# max32620fthr.net
KiCad netlist of a schematic drawn in EAGLE
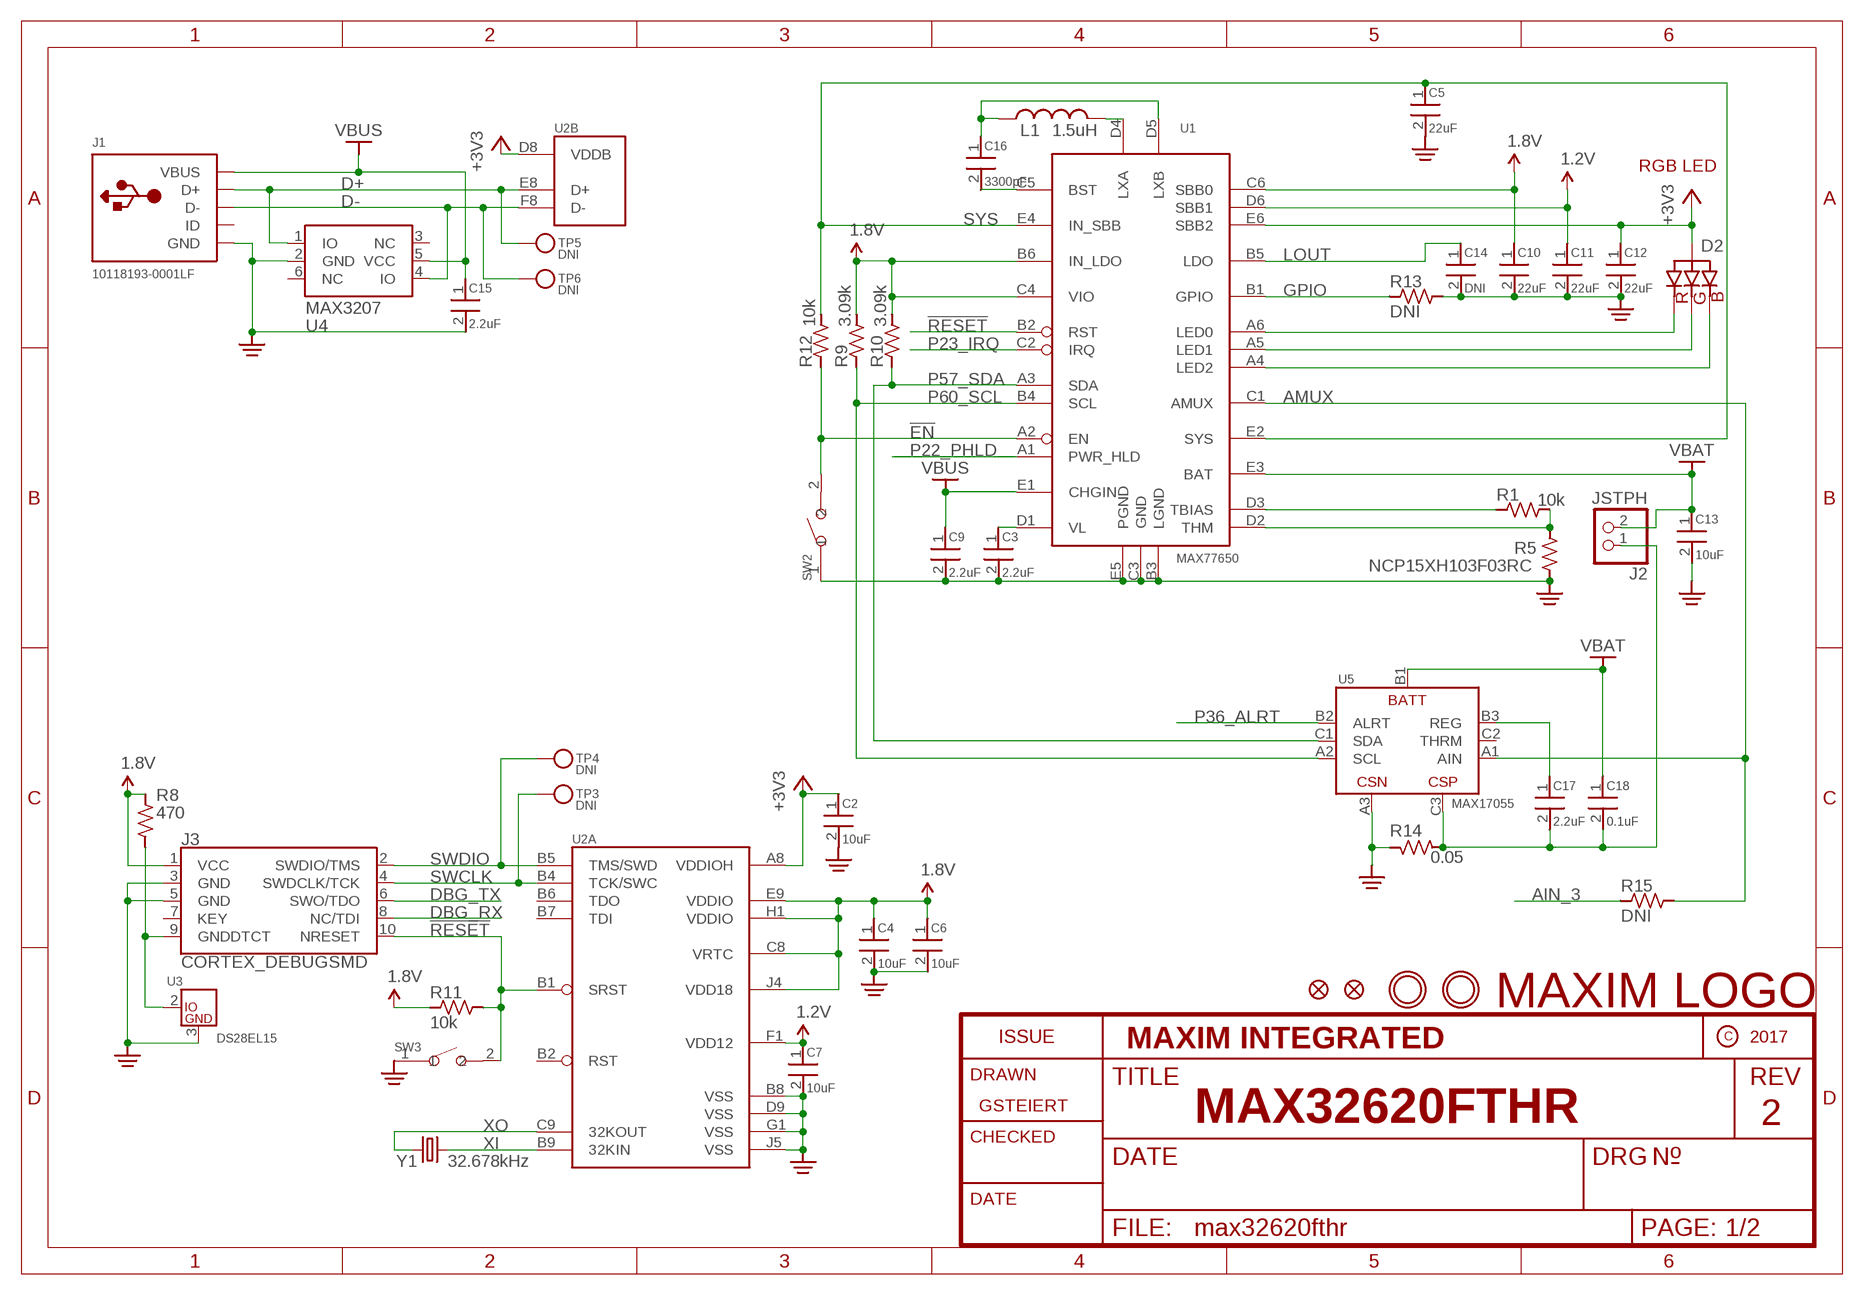
[diagram p0: schematic, sheet 1]
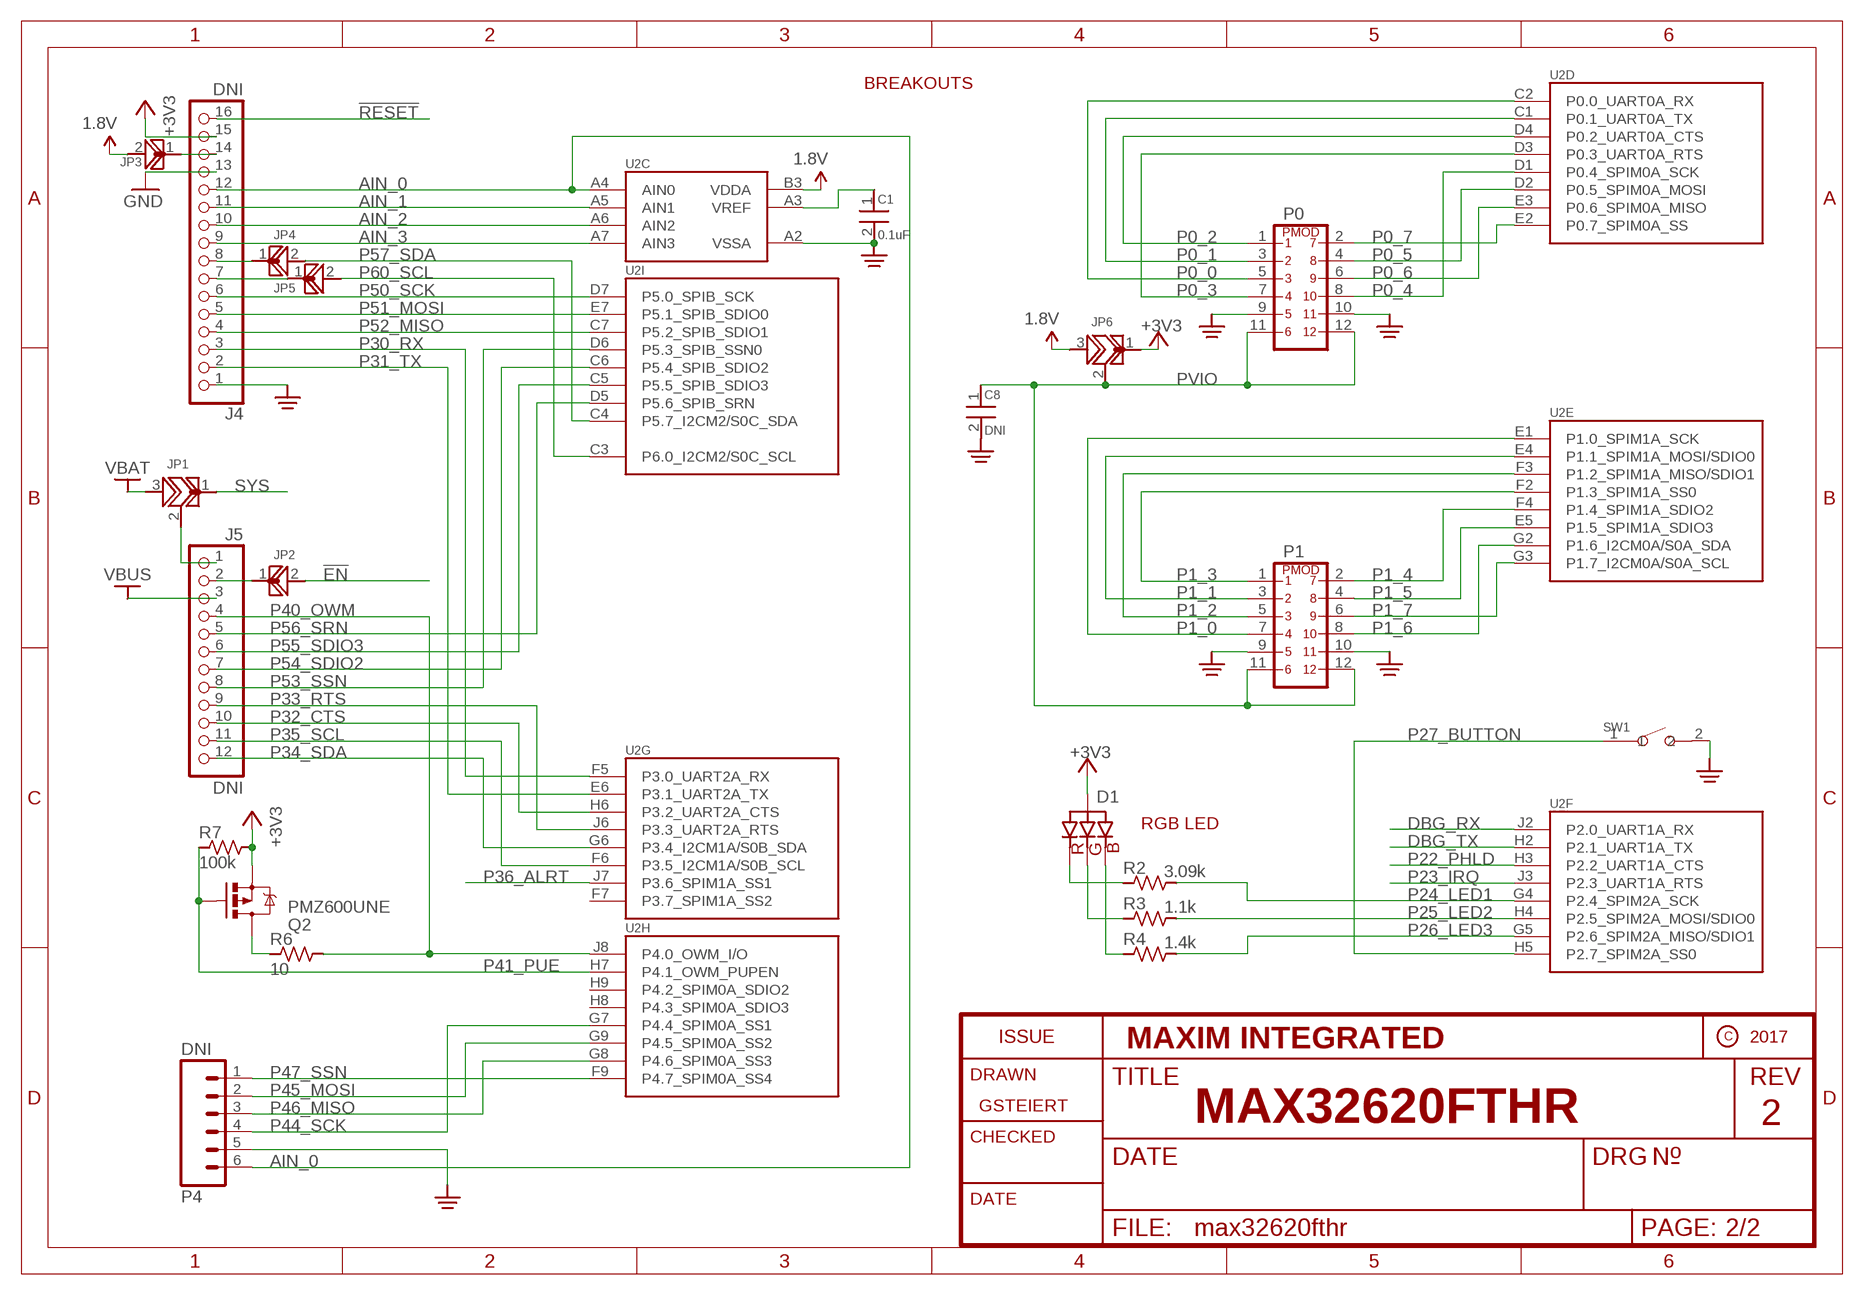
[diagram p1: schematic, sheet 2]

(export (version "E")
  (design (tool "Eeschema 10.0.6"))
  (components
    (comp (ref "C1")
      (value "0.1uF")
      (footprint "eagle-import:0402")
      (libsource (lib "eagle-import") (part "C0402"))
    )
    (comp (ref "C8")
      (value "DNI")
      (footprint "eagle-import:0402")
      (libsource (lib "eagle-import") (part "C0402"))
    )
    (comp (ref "D1")
      (value "RGBLED_CALUMIX-SML-LX0404")
      (footprint "eagle-import:LUMIX-SML-LX0404")
      (libsource (lib "eagle-import") (part "RGBLED_CALUMIX-SML-LX0404"))
    )
    (comp (ref "J4")
      (value "DNI")
      (footprint "eagle-import:1X16_ROUND")
      (libsource (lib "eagle-import") (part "HEADER-1X16ROUND"))
    )
    (comp (ref "J5")
      (value "DNI")
      (footprint "eagle-import:1X12_ROUND")
      (libsource (lib "eagle-import") (part "HEADER-1X12"))
    )
    (comp (ref "JP1")
      (value "DNI")
      (footprint "eagle-import:SS0402")
      (libsource (lib "eagle-import") (part "SOLDER_SELECTOR"))
    )
    (comp (ref "JP2")
      (value "DNI")
      (footprint "eagle-import:SB0402")
      (libsource (lib "eagle-import") (part "SOLDER_BRIDGE"))
    )
    (comp (ref "JP3")
      (value "DNI")
      (footprint "eagle-import:SB0402")
      (libsource (lib "eagle-import") (part "SOLDER_BRIDGE"))
    )
    (comp (ref "JP4")
      (value "DNI")
      (footprint "eagle-import:SB0402")
      (libsource (lib "eagle-import") (part "SOLDER_BRIDGE"))
    )
    (comp (ref "JP5")
      (value "DNI")
      (footprint "eagle-import:SB0402")
      (libsource (lib "eagle-import") (part "SOLDER_BRIDGE"))
    )
    (comp (ref "JP6")
      (value "DNI")
      (footprint "eagle-import:SS0402")
      (libsource (lib "eagle-import") (part "SOLDER_SELECTOR"))
    )
    (comp (ref "P0")
      (value "PMOD_DUALPASSTHROUGH")
      (footprint "eagle-import:2X6_HLE_BE")
      (libsource (lib "eagle-import") (part "PMOD_DUALPASSTHROUGH"))
    )
    (comp (ref "P1")
      (value "PMOD_DUALPASSTHROUGH")
      (footprint "eagle-import:2X6_HLE_BE")
      (libsource (lib "eagle-import") (part "PMOD_DUALPASSTHROUGH"))
    )
    (comp (ref "P4")
      (value "DNI")
      (footprint "eagle-import:1X06-SMD_EDGE")
      (libsource (lib "eagle-import") (part "M061X06-SMD_EDGE_FEMALE"))
    )
    (comp (ref "Q2")
      (value "PMZ600UNE")
      (footprint "eagle-import:SOT-883")
      (libsource (lib "eagle-import") (part "PMZ600UNE"))
    )
    (comp (ref "R2")
      (value "3.09k")
      (footprint "eagle-import:0402")
      (libsource (lib "eagle-import") (part "R"))
    )
    (comp (ref "R3")
      (value "1.1k")
      (footprint "eagle-import:0402")
      (libsource (lib "eagle-import") (part "R"))
    )
    (comp (ref "R4")
      (value "1.4k")
      (footprint "eagle-import:0402")
      (libsource (lib "eagle-import") (part "R"))
    )
    (comp (ref "R6") (value "10") (footprint "eagle-import:0402") (libsource (lib "eagle-import") (part "R")))
    (comp (ref "R7")
      (value "100k")
      (footprint "eagle-import:0402")
      (libsource (lib "eagle-import") (part "R"))
    )
    (comp (ref "SW1")
      (value "SMD-BUTTON(2P-3.0X2.5X1.2+0.4MM)-B3U-1000P-2P-SMD")
      (footprint "eagle-import:SW2-2.6-3.0X2.5X1.2+0.4MM")
      (libsource (lib "eagle-import") (part "SMD-BUTTON(2P-3.0X2.5X1.2+0.4MM)-B3U-1000P-2P-SMD"))
    )
    (comp (ref "U2")
      (value "MAX32620")
      (footprint "eagle-import:W813D3-1")
      (libsource (lib "eagle-import") (part "MAX32620"))
    )
    (comp (ref "C2")
      (value "10uF")
      (footprint "eagle-import:0402")
      (libsource (lib "eagle-import") (part "C0402"))
    )
    (comp (ref "C3")
      (value "2.2uF")
      (footprint "eagle-import:0402")
      (libsource (lib "eagle-import") (part "C0402"))
    )
    (comp (ref "C4")
      (value "10uF")
      (footprint "eagle-import:0402")
      (libsource (lib "eagle-import") (part "C0402"))
    )
    (comp (ref "C5")
      (value "22uF")
      (footprint "eagle-import:0402")
      (libsource (lib "eagle-import") (part "C0402"))
    )
    (comp (ref "C6")
      (value "10uF")
      (footprint "eagle-import:0402")
      (libsource (lib "eagle-import") (part "C0402"))
    )
    (comp (ref "C7")
      (value "10uF")
      (footprint "eagle-import:0402")
      (libsource (lib "eagle-import") (part "C0402"))
    )
    (comp (ref "C9")
      (value "2.2uF")
      (footprint "eagle-import:0402")
      (libsource (lib "eagle-import") (part "C0402"))
    )
    (comp (ref "C10")
      (value "22uF")
      (footprint "eagle-import:0402")
      (libsource (lib "eagle-import") (part "C0402"))
    )
    (comp (ref "C11")
      (value "22uF")
      (footprint "eagle-import:0402")
      (libsource (lib "eagle-import") (part "C0402"))
    )
    (comp (ref "C12")
      (value "22uF")
      (footprint "eagle-import:0402")
      (libsource (lib "eagle-import") (part "C0402"))
    )
    (comp (ref "C13")
      (value "10uF")
      (footprint "eagle-import:0402")
      (libsource (lib "eagle-import") (part "C0402"))
    )
    (comp (ref "C14")
      (value "DNI")
      (footprint "eagle-import:0402")
      (libsource (lib "eagle-import") (part "C0402"))
    )
    (comp (ref "C15")
      (value "2.2uF")
      (footprint "eagle-import:0402")
      (libsource (lib "eagle-import") (part "C0402"))
    )
    (comp (ref "C16")
      (value "3300pF")
      (footprint "eagle-import:0402")
      (libsource (lib "eagle-import") (part "C0402"))
    )
    (comp (ref "C17")
      (value "2.2uF")
      (footprint "eagle-import:0402")
      (libsource (lib "eagle-import") (part "C0402"))
    )
    (comp (ref "C18")
      (value "0.1uF")
      (footprint "eagle-import:0402")
      (libsource (lib "eagle-import") (part "C0402"))
    )
    (comp (ref "D2")
      (value "RGBLED_CALUMIX-SML-LX0404")
      (footprint "eagle-import:LUMIX-SML-LX0404")
      (libsource (lib "eagle-import") (part "RGBLED_CALUMIX-SML-LX0404"))
    )
    (comp (ref "J1")
      (value "10118193-0001LF")
      (footprint "eagle-import:MICRO-USB5+6P-SMD-0.65-B")
      (libsource (lib "eagle-import") (part "MICRO-USB-SMD-B-(10118193-0001LF)"))
    )
    (comp (ref "J2")
      (value "JSTPH")
      (footprint "eagle-import:JSTPH2")
      (libsource (lib "eagle-import") (part "CON_JST_PH_2PIN"))
    )
    (comp (ref "J3")
      (value "CORTEX_DEBUGSMD")
      (footprint "eagle-import:SAMTECH_FTSH-105-01")
      (libsource (lib "eagle-import") (part "CORTEX_DEBUGSMD"))
    )
    (comp (ref "L1")
      (value "1.5uH")
      (footprint "eagle-import:IND2016")
      (libsource (lib "eagle-import") (part "INDUCTOR2016"))
    )
    (comp (ref "R1")
      (value "10k")
      (footprint "eagle-import:0402")
      (libsource (lib "eagle-import") (part "R"))
    )
    (comp (ref "R5")
      (value "NCP15XH103F03RC")
      (footprint "eagle-import:0402")
      (libsource (lib "eagle-import") (part "R"))
    )
    (comp (ref "R8")
      (value "470")
      (footprint "eagle-import:0402")
      (libsource (lib "eagle-import") (part "R"))
    )
    (comp (ref "R9")
      (value "3.09k")
      (footprint "eagle-import:0402")
      (libsource (lib "eagle-import") (part "R"))
    )
    (comp (ref "R10")
      (value "3.09k")
      (footprint "eagle-import:0402")
      (libsource (lib "eagle-import") (part "R"))
    )
    (comp (ref "R11")
      (value "10k")
      (footprint "eagle-import:0402")
      (libsource (lib "eagle-import") (part "R"))
    )
    (comp (ref "R12")
      (value "10k")
      (footprint "eagle-import:0402")
      (libsource (lib "eagle-import") (part "R"))
    )
    (comp (ref "R13")
      (value "DNI")
      (footprint "eagle-import:0402")
      (libsource (lib "eagle-import") (part "R"))
    )
    (comp (ref "R14")
      (value "0.05")
      (footprint "eagle-import:0402")
      (libsource (lib "eagle-import") (part "R"))
    )
    (comp (ref "R15")
      (value "DNI")
      (footprint "eagle-import:0402")
      (libsource (lib "eagle-import") (part "R"))
    )
    (comp (ref "SW2")
      (value "SMD-BUTTON(2P-3.0X2.5X1.2+0.4MM)-B3U-1000P-2P-SMD")
      (footprint "eagle-import:SW2-2.6-3.0X2.5X1.2+0.4MM")
      (libsource (lib "eagle-import") (part "SMD-BUTTON(2P-3.0X2.5X1.2+0.4MM)-B3U-1000P-2P-SMD"))
    )
    (comp (ref "SW3")
      (value "SMD-BUTTON(2P-3.0X2.5X1.2+0.4MM)-B3U-1000P-2P-SMD")
      (footprint "eagle-import:SW2-2.6-3.0X2.5X1.2+0.4MM")
      (libsource (lib "eagle-import") (part "SMD-BUTTON(2P-3.0X2.5X1.2+0.4MM)-B3U-1000P-2P-SMD"))
    )
    (comp (ref "TP3")
      (value "DNI")
      (footprint "eagle-import:TESTPOINT_ROUND_1MM")
      (libsource (lib "eagle-import") (part "TESTPOINTROUND1MM"))
    )
    (comp (ref "TP4")
      (value "DNI")
      (footprint "eagle-import:TESTPOINT_ROUND_1MM")
      (libsource (lib "eagle-import") (part "TESTPOINTROUND1MM"))
    )
    (comp (ref "TP5")
      (value "DNI")
      (footprint "eagle-import:TESTPOINT_ROUND_1MM")
      (libsource (lib "eagle-import") (part "TESTPOINTROUND1MM"))
    )
    (comp (ref "TP6")
      (value "DNI")
      (footprint "eagle-import:TESTPOINT_ROUND_1MM")
      (libsource (lib "eagle-import") (part "TESTPOINTROUND1MM"))
    )
    (comp (ref "U$3")
      (value "DNI")
      (footprint "eagle-import:MXM_LOGO_6MM")
      (libsource (lib "eagle-import") (part "MAXIM_LOGO"))
    )
    (comp (ref "U$31")
      (value "DNI")
      (footprint "eagle-import:MOUNTINGHOLE_2.5_PLATED")
      (libsource (lib "eagle-import") (part "MOUNTINGHOLE2.5"))
    )
    (comp (ref "U$32")
      (value "DNI")
      (footprint "eagle-import:MOUNTINGHOLE_2.5_PLATED")
      (libsource (lib "eagle-import") (part "MOUNTINGHOLE2.5"))
    )
    (comp (ref "U$34")
      (value "DNI")
      (footprint "eagle-import:FIDUCIAL_1MM")
      (libsource (lib "eagle-import") (part "FIDUCIAL{dblquote}{dblquote}"))
    )
    (comp (ref "U$35")
      (value "DNI")
      (footprint "eagle-import:FIDUCIAL_1MM")
      (libsource (lib "eagle-import") (part "FIDUCIAL{dblquote}{dblquote}"))
    )
    (comp (ref "U1")
      (value "MAX77650")
      (footprint "eagle-import:W302H2-1")
      (libsource (lib "eagle-import") (part "MAX77650"))
    )
    (comp (ref "U3")
      (value "DS28EL15")
      (footprint "eagle-import:T633-2")
      (libsource (lib "eagle-import") (part "DS28EL15"))
    )
    (comp (ref "U4")
      (value "MAX3207")
      (footprint "eagle-import:SOT23-6")
      (libsource (lib "eagle-import") (part "MAX3207"))
    )
    (comp (ref "U5")
      (value "MAX17055")
      (footprint "eagle-import:W91N1-1")
      (libsource (lib "eagle-import") (part "MAX17055"))
    )
    (comp (ref "Y1")
      (value "32.678kHz")
      (footprint "eagle-import:FC-12M")
      (libsource (lib "eagle-import") (part "FC-12M"))
    )
  )
  (nets
    (net (code "1") (name "+3V3") (class "Default")
      (node (ref "C12") (pin "1") (pinfunction "1_1") (pintype "bidirectional"))
      (node (ref "C2") (pin "1") (pinfunction "1_1") (pintype "bidirectional"))
      (node (ref "D1") (pin "1") (pinfunction "VCC_1") (pintype "bidirectional"))
      (node (ref "D2") (pin "1") (pinfunction "VCC_1") (pintype "bidirectional"))
      (node (ref "J4") (pin "15") (pinfunction "15_15") (pintype "passive"))
      (node (ref "JP6") (pin "1") (pinfunction "1_1") (pintype "bidirectional"))
      (node (ref "Q2") (pin "2") (pinfunction "S_2") (pintype "passive"))
      (node (ref "R7") (pin "2") (pinfunction "2_2") (pintype "passive"))
      (node (ref "U1") (pin "E6") (pinfunction "SBB2_E6") (pintype "power_in"))
      (node (ref "U2") (pin "A8") (pinfunction "VDDIOH_A8") (pintype "power_in"))
      (node (ref "U2") (pin "D8") (pinfunction "VDDB_D8") (pintype "power_in"))
    )
    (net (code "2") (name "1.2V") (class "Default")
      (node (ref "C11") (pin "1") (pinfunction "1_1") (pintype "bidirectional"))
      (node (ref "C7") (pin "1") (pinfunction "1_1") (pintype "bidirectional"))
      (node (ref "U1") (pin "D6") (pinfunction "SBB1_D6") (pintype "power_in"))
      (node (ref "U2") (pin "F1") (pinfunction "VDD12_F1") (pintype "power_in"))
    )
    (net (code "3") (name "1.8V") (class "Default")
      (node (ref "C10") (pin "1") (pinfunction "1_1") (pintype "bidirectional"))
      (node (ref "C4") (pin "1") (pinfunction "1_1") (pintype "bidirectional"))
      (node (ref "C6") (pin "1") (pinfunction "1_1") (pintype "bidirectional"))
      (node (ref "J3") (pin "1") (pinfunction "VCC_1") (pintype "bidirectional"))
      (node (ref "JP3") (pin "2") (pinfunction "2_2") (pintype "bidirectional"))
      (node (ref "JP6") (pin "3") (pinfunction "3_3") (pintype "bidirectional"))
      (node (ref "R10") (pin "2") (pinfunction "2_2") (pintype "passive"))
      (node (ref "R11") (pin "1") (pinfunction "1_1") (pintype "passive"))
      (node (ref "R8") (pin "2") (pinfunction "2_2") (pintype "passive"))
      (node (ref "R9") (pin "2") (pinfunction "2_2") (pintype "passive"))
      (node (ref "U1") (pin "B6") (pinfunction "IN_LDO_B6") (pintype "power_in"))
      (node (ref "U1") (pin "C4") (pinfunction "VIO_C4") (pintype "power_in"))
      (node (ref "U1") (pin "C6") (pinfunction "SBB0_C6") (pintype "power_in"))
      (node (ref "U2") (pin "B3") (pinfunction "VDDA_B3") (pintype "power_in"))
      (node (ref "U2") (pin "C8") (pinfunction "VRTC_C8") (pintype "power_in"))
      (node (ref "U2") (pin "E9") (pinfunction "VDDIO_E9") (pintype "power_in"))
      (node (ref "U2") (pin "H1") (pinfunction "VDDIO_H1") (pintype "power_in"))
      (node (ref "U2") (pin "J4") (pinfunction "VDD18_J4") (pintype "power_in"))
    )
    (net (code "4") (name "AIN_0") (class "Default")
      (node (ref "J4") (pin "12") (pinfunction "12_12") (pintype "passive"))
      (node (ref "P4") (pin "6") (pinfunction "6_6") (pintype "passive"))
      (node (ref "U2") (pin "A4") (pinfunction "AIN0_A4") (pintype "input"))
    )
    (net (code "5") (name "AIN_1") (class "Default")
      (node (ref "J4") (pin "11") (pinfunction "11_11") (pintype "passive"))
      (node (ref "U2") (pin "A5") (pinfunction "AIN1_A5") (pintype "input"))
    )
    (net (code "6") (name "AIN_2") (class "Default")
      (node (ref "J4") (pin "10") (pinfunction "10_10") (pintype "passive"))
      (node (ref "U2") (pin "A6") (pinfunction "AIN2_A6") (pintype "input"))
    )
    (net (code "7") (name "AIN_3") (class "Default")
      (node (ref "J4") (pin "9") (pinfunction "9_9") (pintype "passive"))
      (node (ref "R15") (pin "1") (pinfunction "1_1") (pintype "passive"))
      (node (ref "U2") (pin "A7") (pinfunction "AIN3_A7") (pintype "input"))
    )
    (net (code "8") (name "AMUX") (class "Default")
      (node (ref "R15") (pin "2") (pinfunction "2_2") (pintype "passive"))
      (node (ref "U1") (pin "C1") (pinfunction "AMUX_C1") (pintype "output"))
      (node (ref "U5") (pin "A1") (pinfunction "AIN_A1") (pintype "input"))
    )
    (net (code "9") (name "D+") (class "Default")
      (node (ref "J1") (pin "3") (pinfunction "D+_3") (pintype "bidirectional"))
      (node (ref "TP5") (pin "P$1") (pinfunction "P$1_P$1") (pintype "bidirectional"))
      (node (ref "U2") (pin "E8") (pinfunction "D+_E8") (pintype "bidirectional"))
      (node (ref "U4") (pin "1") (pinfunction "IO_1") (pintype "bidirectional"))
    )
    (net (code "10") (name "D-") (class "Default")
      (node (ref "J1") (pin "2") (pinfunction "D-_2") (pintype "bidirectional"))
      (node (ref "TP6") (pin "P$1") (pinfunction "P$1_P$1") (pintype "bidirectional"))
      (node (ref "U2") (pin "F8") (pinfunction "D-_F8") (pintype "bidirectional"))
      (node (ref "U4") (pin "4") (pinfunction "IO_4") (pintype "bidirectional"))
    )
    (net (code "11") (name "DBG_RX") (class "Default")
      (node (ref "J3") (pin "8") (pinfunction "NC/TDI_8") (pintype "bidirectional"))
      (node (ref "U2") (pin "J2") (pinfunction "P2.0_UART1A_RX_J2") (pintype "bidirectional"))
    )
    (net (code "12") (name "DBG_TX") (class "Default")
      (node (ref "J3") (pin "6") (pinfunction "SWO/TDO_6") (pintype "bidirectional"))
      (node (ref "U2") (pin "H2") (pinfunction "P2.1_UART1A_TX_H2") (pintype "bidirectional"))
    )
    (net (code "13") (name "GND") (class "Default")
      (node (ref "C1") (pin "2") (pinfunction "2_2") (pintype "bidirectional"))
      (node (ref "C10") (pin "2") (pinfunction "2_2") (pintype "bidirectional"))
      (node (ref "C11") (pin "2") (pinfunction "2_2") (pintype "bidirectional"))
      (node (ref "C12") (pin "2") (pinfunction "2_2") (pintype "bidirectional"))
      (node (ref "C13") (pin "2") (pinfunction "2_2") (pintype "bidirectional"))
      (node (ref "C14") (pin "2") (pinfunction "2_2") (pintype "bidirectional"))
      (node (ref "C15") (pin "2") (pinfunction "2_2") (pintype "bidirectional"))
      (node (ref "C2") (pin "2") (pinfunction "2_2") (pintype "bidirectional"))
      (node (ref "C3") (pin "2") (pinfunction "2_2") (pintype "bidirectional"))
      (node (ref "C4") (pin "2") (pinfunction "2_2") (pintype "bidirectional"))
      (node (ref "C5") (pin "2") (pinfunction "2_2") (pintype "bidirectional"))
      (node (ref "C6") (pin "2") (pinfunction "2_2") (pintype "bidirectional"))
      (node (ref "C7") (pin "2") (pinfunction "2_2") (pintype "bidirectional"))
      (node (ref "C8") (pin "2") (pinfunction "2_2") (pintype "bidirectional"))
      (node (ref "C9") (pin "2") (pinfunction "2_2") (pintype "bidirectional"))
      (node (ref "J1") (pin "5") (pinfunction "GND_5") (pintype "power_in"))
      (node (ref "J1") (pin "S1") (pinfunction "GND_S1") (pintype "power_in"))
      (node (ref "J1") (pin "S2") (pinfunction "GND_S2") (pintype "power_in"))
      (node (ref "J1") (pin "S3") (pinfunction "GND_S3") (pintype "power_in"))
      (node (ref "J1") (pin "S4") (pinfunction "GND_S4") (pintype "power_in"))
      (node (ref "J1") (pin "S5") (pinfunction "GND_S5") (pintype "power_in"))
      (node (ref "J1") (pin "S6") (pinfunction "GND_S6") (pintype "power_in"))
      (node (ref "J3") (pin "3") (pinfunction "GND_3") (pintype "bidirectional"))
      (node (ref "J3") (pin "5") (pinfunction "GND_5") (pintype "bidirectional"))
      (node (ref "J4") (pin "1") (pinfunction "1_1") (pintype "passive"))
      (node (ref "J4") (pin "13") (pinfunction "13_13") (pintype "passive"))
      (node (ref "P0") (pin "10") (pinfunction "10_10") (pintype "passive"))
      (node (ref "P0") (pin "9") (pinfunction "9_9") (pintype "passive"))
      (node (ref "P1") (pin "10") (pinfunction "10_10") (pintype "passive"))
      (node (ref "P1") (pin "9") (pinfunction "9_9") (pintype "passive"))
      (node (ref "P4") (pin "5") (pinfunction "5_5") (pintype "passive"))
      (node (ref "R13") (pin "2") (pinfunction "2_2") (pintype "passive"))
      (node (ref "R14") (pin "2") (pinfunction "2_2") (pintype "passive"))
      (node (ref "R5") (pin "2") (pinfunction "2_2") (pintype "passive"))
      (node (ref "SW1") (pin "2") (pinfunction "2_2") (pintype "bidirectional"))
      (node (ref "SW2") (pin "1") (pinfunction "1_1") (pintype "bidirectional"))
      (node (ref "SW3") (pin "1") (pinfunction "1_1") (pintype "bidirectional"))
      (node (ref "U1") (pin "B3") (pinfunction "LGND_B3") (pintype "power_in"))
      (node (ref "U1") (pin "C3") (pinfunction "GND_C3") (pintype "power_in"))
      (node (ref "U1") (pin "E5") (pinfunction "PGND_E5") (pintype "power_in"))
      (node (ref "U2") (pin "A2") (pinfunction "VSSA_A2") (pintype "power_in"))
      (node (ref "U2") (pin "B8") (pinfunction "VSS_B8") (pintype "power_in"))
      (node (ref "U2") (pin "D9") (pinfunction "VSS_D9") (pintype "power_in"))
      (node (ref "U2") (pin "G1") (pinfunction "VSS_G1") (pintype "power_in"))
      (node (ref "U2") (pin "J5") (pinfunction "VSS_J5") (pintype "power_in"))
      (node (ref "U3") (pin "3") (pinfunction "GND_3") (pintype "power_in"))
      (node (ref "U4") (pin "2") (pinfunction "GND_2") (pintype "power_in"))
      (node (ref "U5") (pin "A3") (pinfunction "CSN_A3") (pintype "output"))
    )
    (net (code "14") (name "GPIO") (class "Default")
      (node (ref "R13") (pin "1") (pinfunction "1_1") (pintype "passive"))
      (node (ref "U1") (pin "B1") (pinfunction "GPIO_B1") (pintype "bidirectional"))
    )
    (net (code "15") (name "LOUT") (class "Default")
      (node (ref "C14") (pin "1") (pinfunction "1_1") (pintype "bidirectional"))
      (node (ref "U1") (pin "B5") (pinfunction "LDO_B5") (pintype "power_in"))
    )
    (net (code "16") (name "Net-(D1-BLUE)") (class "Default")
      (node (ref "D1") (pin "3") (pinfunction "BLUE_3") (pintype "bidirectional"))
      (node (ref "R4") (pin "1") (pinfunction "1_1") (pintype "passive"))
    )
    (net (code "17") (name "Net-(D1-GREEN)") (class "Default")
      (node (ref "D1") (pin "4") (pinfunction "GREEN_4") (pintype "bidirectional"))
      (node (ref "R3") (pin "1") (pinfunction "1_1") (pintype "passive"))
    )
    (net (code "18") (name "Net-(D1-RED)") (class "Default")
      (node (ref "D1") (pin "2") (pinfunction "RED_2") (pintype "bidirectional"))
      (node (ref "R2") (pin "1") (pinfunction "1_1") (pintype "passive"))
    )
    (net (code "19") (name "Net-(D2-BLUE)") (class "Default")
      (node (ref "D2") (pin "3") (pinfunction "BLUE_3") (pintype "bidirectional"))
      (node (ref "U1") (pin "A4") (pinfunction "LED2_A4") (pintype "output"))
    )
    (net (code "20") (name "Net-(D2-GREEN)") (class "Default")
      (node (ref "D2") (pin "4") (pinfunction "GREEN_4") (pintype "bidirectional"))
      (node (ref "U1") (pin "A5") (pinfunction "LED1_A5") (pintype "output"))
    )
    (net (code "21") (name "Net-(D2-RED)") (class "Default")
      (node (ref "D2") (pin "2") (pinfunction "RED_2") (pintype "bidirectional"))
      (node (ref "U1") (pin "A6") (pinfunction "LED0_A6") (pintype "output"))
    )
    (net (code "22") (name "Net-(J3-GNDDTCT)") (class "Default")
      (node (ref "J3") (pin "9") (pinfunction "GNDDTCT_9") (pintype "bidirectional"))
      (node (ref "R8") (pin "1") (pinfunction "1_1") (pintype "passive"))
      (node (ref "U3") (pin "2") (pinfunction "IO_2") (pintype "bidirectional"))
    )
    (net (code "23") (name "Net-(J4-Pad7)") (class "Default")
      (node (ref "J4") (pin "7") (pinfunction "7_7") (pintype "passive"))
      (node (ref "JP5") (pin "1") (pinfunction "1_1") (pintype "bidirectional"))
    )
    (net (code "24") (name "Net-(J4-Pad8)") (class "Default")
      (node (ref "J4") (pin "8") (pinfunction "8_8") (pintype "passive"))
      (node (ref "JP4") (pin "1") (pinfunction "1_1") (pintype "bidirectional"))
    )
    (net (code "25") (name "Net-(J4-Pad14)") (class "Default")
      (node (ref "J4") (pin "14") (pinfunction "14_14") (pintype "passive"))
      (node (ref "JP3") (pin "1") (pinfunction "1_1") (pintype "bidirectional"))
    )
    (net (code "26") (name "Net-(J5-Pad1)") (class "Default")
      (node (ref "J5") (pin "1") (pinfunction "1_1") (pintype "passive"))
      (node (ref "JP1") (pin "2") (pinfunction "2_2") (pintype "bidirectional"))
    )
    (net (code "27") (name "Net-(J5-Pad2)") (class "Default")
      (node (ref "J5") (pin "2") (pinfunction "2_2") (pintype "passive"))
      (node (ref "JP2") (pin "1") (pinfunction "1_1") (pintype "bidirectional"))
    )
    (net (code "28") (name "Net-(Q2-D)") (class "Default")
      (node (ref "Q2") (pin "3") (pinfunction "D_3") (pintype "passive"))
      (node (ref "R6") (pin "1") (pinfunction "1_1") (pintype "passive"))
    )
    (net (code "29") (name "Net-(U1-BST)") (class "Default")
      (node (ref "C16") (pin "2") (pinfunction "2_2") (pintype "bidirectional"))
      (node (ref "U1") (pin "C5") (pinfunction "BST_C5") (pintype "power_in"))
    )
    (net (code "30") (name "Net-(U1-LXA)") (class "Default")
      (node (ref "L1") (pin "2") (pinfunction "2_2") (pintype "passive"))
      (node (ref "U1") (pin "D4") (pinfunction "LXA_D4") (pintype "power_in"))
    )
    (net (code "31") (name "Net-(U1-LXB)") (class "Default")
      (node (ref "C16") (pin "1") (pinfunction "1_1") (pintype "bidirectional"))
      (node (ref "L1") (pin "1") (pinfunction "1_1") (pintype "passive"))
      (node (ref "U1") (pin "D5") (pinfunction "LXB_D5") (pintype "power_in"))
    )
    (net (code "32") (name "Net-(U1-TBIAS)") (class "Default")
      (node (ref "R1") (pin "1") (pinfunction "1_1") (pintype "passive"))
      (node (ref "U1") (pin "D3") (pinfunction "TBIAS_D3") (pintype "output"))
    )
    (net (code "33") (name "Net-(U1-THM)") (class "Default")
      (node (ref "R1") (pin "2") (pinfunction "2_2") (pintype "passive"))
      (node (ref "R5") (pin "1") (pinfunction "1_1") (pintype "passive"))
      (node (ref "U1") (pin "D2") (pinfunction "THM_D2") (pintype "input"))
    )
    (net (code "34") (name "Net-(U1-VL)") (class "Default")
      (node (ref "C3") (pin "1") (pinfunction "1_1") (pintype "bidirectional"))
      (node (ref "U1") (pin "D1") (pinfunction "VL_D1") (pintype "power_in"))
    )
    (net (code "35") (name "Net-(U2C-VREF)") (class "Default")
      (node (ref "C1") (pin "1") (pinfunction "1_1") (pintype "bidirectional"))
      (node (ref "U2") (pin "A3") (pinfunction "VREF_A3") (pintype "power_in"))
    )
    (net (code "36") (name "Net-(U5-CSP)") (class "Default")
      (node (ref "C17") (pin "2") (pinfunction "2_2") (pintype "bidirectional"))
      (node (ref "C18") (pin "2") (pinfunction "2_2") (pintype "bidirectional"))
      (node (ref "J2") (pin "1") (pinfunction "1_1") (pintype "passive"))
      (node (ref "R14") (pin "1") (pinfunction "1_1") (pintype "passive"))
      (node (ref "U5") (pin "C3") (pinfunction "CSP_C3") (pintype "power_in"))
    )
    (net (code "37") (name "Net-(U5-REG)") (class "Default")
      (node (ref "C17") (pin "1") (pinfunction "1_1") (pintype "bidirectional"))
      (node (ref "U5") (pin "B3") (pinfunction "REG_B3") (pintype "power_in"))
    )
    (net (code "38") (name "P0_0") (class "Default")
      (node (ref "P0") (pin "5") (pinfunction "5_5") (pintype "passive"))
      (node (ref "U2") (pin "C2") (pinfunction "P0.0_UART0A_RX_C2") (pintype "bidirectional"))
    )
    (net (code "39") (name "P0_1") (class "Default")
      (node (ref "P0") (pin "3") (pinfunction "3_3") (pintype "passive"))
      (node (ref "U2") (pin "C1") (pinfunction "P0.1_UART0A_TX_C1") (pintype "bidirectional"))
    )
    (net (code "40") (name "P0_2") (class "Default")
      (node (ref "P0") (pin "1") (pinfunction "1_1") (pintype "passive"))
      (node (ref "U2") (pin "D4") (pinfunction "P0.2_UART0A_CTS_D4") (pintype "bidirectional"))
    )
    (net (code "41") (name "P0_3") (class "Default")
      (node (ref "P0") (pin "7") (pinfunction "7_7") (pintype "passive"))
      (node (ref "U2") (pin "D3") (pinfunction "P0.3_UART0A_RTS_D3") (pintype "bidirectional"))
    )
    (net (code "42") (name "P0_4") (class "Default")
      (node (ref "P0") (pin "8") (pinfunction "8_8") (pintype "passive"))
      (node (ref "U2") (pin "D1") (pinfunction "P0.4_SPIM0A_SCK_D1") (pintype "bidirectional"))
    )
    (net (code "43") (name "P0_5") (class "Default")
      (node (ref "P0") (pin "4") (pinfunction "4_4") (pintype "passive"))
      (node (ref "U2") (pin "D2") (pinfunction "P0.5_SPIM0A_MOSI_D2") (pintype "bidirectional"))
    )
    (net (code "44") (name "P0_6") (class "Default")
      (node (ref "P0") (pin "6") (pinfunction "6_6") (pintype "passive"))
      (node (ref "U2") (pin "E3") (pinfunction "P0.6_SPIM0A_MISO_E3") (pintype "bidirectional"))
    )
    (net (code "45") (name "P0_7") (class "Default")
      (node (ref "P0") (pin "2") (pinfunction "2_2") (pintype "passive"))
      (node (ref "U2") (pin "E2") (pinfunction "P0.7_SPIM0A_SS_E2") (pintype "bidirectional"))
    )
    (net (code "46") (name "P1_0") (class "Default")
      (node (ref "P1") (pin "7") (pinfunction "7_7") (pintype "passive"))
      (node (ref "U2") (pin "E1") (pinfunction "P1.0_SPIM1A_SCK_E1") (pintype "bidirectional"))
    )
    (net (code "47") (name "P1_1") (class "Default")
      (node (ref "P1") (pin "3") (pinfunction "3_3") (pintype "passive"))
      (node (ref "U2") (pin "E4") (pinfunction "P1.1_SPIM1A_MOSI/SDIO0_E4") (pintype "bidirectional"))
    )
    (net (code "48") (name "P1_2") (class "Default")
      (node (ref "P1") (pin "5") (pinfunction "5_5") (pintype "passive"))
      (node (ref "U2") (pin "F3") (pinfunction "P1.2_SPIM1A_MISO/SDIO1_F3") (pintype "bidirectional"))
    )
    (net (code "49") (name "P1_3") (class "Default")
      (node (ref "P1") (pin "1") (pinfunction "1_1") (pintype "passive"))
      (node (ref "U2") (pin "F2") (pinfunction "P1.3_SPIM1A_SS0_F2") (pintype "bidirectional"))
    )
    (net (code "50") (name "P1_4") (class "Default")
      (node (ref "P1") (pin "2") (pinfunction "2_2") (pintype "passive"))
      (node (ref "U2") (pin "F4") (pinfunction "P1.4_SPIM1A_SDIO2_F4") (pintype "bidirectional"))
    )
    (net (code "51") (name "P1_5") (class "Default")
      (node (ref "P1") (pin "4") (pinfunction "4_4") (pintype "passive"))
      (node (ref "U2") (pin "E5") (pinfunction "P1.5_SPIM1A_SDIO3_E5") (pintype "bidirectional"))
    )
    (net (code "52") (name "P1_6") (class "Default")
      (node (ref "P1") (pin "8") (pinfunction "8_8") (pintype "passive"))
      (node (ref "U2") (pin "G2") (pinfunction "P1.6_I2CM0A/S0A_SDA_G2") (pintype "bidirectional"))
    )
    (net (code "53") (name "P1_7") (class "Default")
      (node (ref "P1") (pin "6") (pinfunction "6_6") (pintype "passive"))
      (node (ref "U2") (pin "G3") (pinfunction "P1.7_I2CM0A/S0A_SCL_G3") (pintype "bidirectional"))
    )
    (net (code "54") (name "P22_PHLD") (class "Default")
      (node (ref "U1") (pin "A1") (pinfunction "PWR_HLD_A1") (pintype "open_collector"))
      (node (ref "U2") (pin "H3") (pinfunction "P2.2_UART1A_CTS_H3") (pintype "bidirectional"))
    )
    (net (code "55") (name "P23_IRQ") (class "Default")
      (node (ref "U1") (pin "C2") (pinfunction "IRQ_C2") (pintype "output"))
      (node (ref "U2") (pin "J3") (pinfunction "P2.3_UART1A_RTS_J3") (pintype "bidirectional"))
    )
    (net (code "56") (name "P24_LED1") (class "Default")
      (node (ref "R2") (pin "2") (pinfunction "2_2") (pintype "passive"))
      (node (ref "U2") (pin "G4") (pinfunction "P2.4_SPIM2A_SCK_G4") (pintype "bidirectional"))
    )
    (net (code "57") (name "P25_LED2") (class "Default")
      (node (ref "R3") (pin "2") (pinfunction "2_2") (pintype "passive"))
      (node (ref "U2") (pin "H4") (pinfunction "P2.5_SPIM2A_MOSI/SDIO0_H4") (pintype "bidirectional"))
    )
    (net (code "58") (name "P26_LED3") (class "Default")
      (node (ref "R4") (pin "2") (pinfunction "2_2") (pintype "passive"))
      (node (ref "U2") (pin "G5") (pinfunction "P2.6_SPIM2A_MISO/SDIO1_G5") (pintype "bidirectional"))
    )
    (net (code "59") (name "P27_BUTTON") (class "Default")
      (node (ref "SW1") (pin "1") (pinfunction "1_1") (pintype "bidirectional"))
      (node (ref "U2") (pin "H5") (pinfunction "P2.7_SPIM2A_SS0_H5") (pintype "bidirectional"))
    )
    (net (code "60") (name "P30_RX") (class "Default")
      (node (ref "J4") (pin "3") (pinfunction "3_3") (pintype "passive"))
      (node (ref "U2") (pin "F5") (pinfunction "P3.0_UART2A_RX_F5") (pintype "bidirectional"))
    )
    (net (code "61") (name "P31_TX") (class "Default")
      (node (ref "J4") (pin "2") (pinfunction "2_2") (pintype "passive"))
      (node (ref "U2") (pin "E6") (pinfunction "P3.1_UART2A_TX_E6") (pintype "bidirectional"))
    )
    (net (code "62") (name "P32_CTS") (class "Default")
      (node (ref "J5") (pin "10") (pinfunction "10_10") (pintype "passive"))
      (node (ref "U2") (pin "H6") (pinfunction "P3.2_UART2A_CTS_H6") (pintype "bidirectional"))
    )
    (net (code "63") (name "P33_RTS") (class "Default")
      (node (ref "J5") (pin "9") (pinfunction "9_9") (pintype "passive"))
      (node (ref "U2") (pin "J6") (pinfunction "P3.3_UART2A_RTS_J6") (pintype "bidirectional"))
    )
    (net (code "64") (name "P34_SDA") (class "Default")
      (node (ref "J5") (pin "12") (pinfunction "12_12") (pintype "passive"))
      (node (ref "U2") (pin "G6") (pinfunction "P3.4_I2CM1A/S0B_SDA_G6") (pintype "bidirectional"))
    )
    (net (code "65") (name "P35_SCL") (class "Default")
      (node (ref "J5") (pin "11") (pinfunction "11_11") (pintype "passive"))
      (node (ref "U2") (pin "F6") (pinfunction "P3.5_I2CM1A/S0B_SCL_F6") (pintype "bidirectional"))
    )
    (net (code "66") (name "P36_ALRT") (class "Default")
      (node (ref "U2") (pin "J7") (pinfunction "P3.6_SPIM1A_SS1_J7") (pintype "bidirectional"))
      (node (ref "U5") (pin "B2") (pinfunction "ALRT_B2") (pintype "output"))
    )
    (net (code "67") (name "P40_OWM") (class "Default")
      (node (ref "J5") (pin "4") (pinfunction "4_4") (pintype "passive"))
      (node (ref "R6") (pin "2") (pinfunction "2_2") (pintype "passive"))
      (node (ref "U2") (pin "J8") (pinfunction "P4.0_OWM_I/O_J8") (pintype "bidirectional"))
    )
    (net (code "68") (name "P41_PUE") (class "Default")
      (node (ref "Q2") (pin "1") (pinfunction "G_1") (pintype "passive"))
      (node (ref "R7") (pin "1") (pinfunction "1_1") (pintype "passive"))
      (node (ref "U2") (pin "H7") (pinfunction "P4.1_OWM_PUPEN_H7") (pintype "bidirectional"))
    )
    (net (code "69") (name "P44_SCK") (class "Default")
      (node (ref "P4") (pin "4") (pinfunction "4_4") (pintype "passive"))
      (node (ref "U2") (pin "G7") (pinfunction "P4.4_SPIM0A_SS1_G7") (pintype "bidirectional"))
    )
    (net (code "70") (name "P45_MOSI") (class "Default")
      (node (ref "P4") (pin "2") (pinfunction "2_2") (pintype "passive"))
      (node (ref "U2") (pin "G9") (pinfunction "P4.5_SPIM0A_SS2_G9") (pintype "bidirectional"))
    )
    (net (code "71") (name "P46_MISO") (class "Default")
      (node (ref "P4") (pin "3") (pinfunction "3_3") (pintype "passive"))
      (node (ref "U2") (pin "G8") (pinfunction "P4.6_SPIM0A_SS3_G8") (pintype "bidirectional"))
    )
    (net (code "72") (name "P47_SSN") (class "Default")
      (node (ref "P4") (pin "1") (pinfunction "1_1") (pintype "passive"))
      (node (ref "U2") (pin "F9") (pinfunction "P4.7_SPIM0A_SS4_F9") (pintype "bidirectional"))
    )
    (net (code "73") (name "P50_SCK") (class "Default")
      (node (ref "J4") (pin "6") (pinfunction "6_6") (pintype "passive"))
      (node (ref "U2") (pin "D7") (pinfunction "P5.0_SPIB_SCK_D7") (pintype "bidirectional"))
    )
    (net (code "74") (name "P51_MOSI") (class "Default")
      (node (ref "J4") (pin "5") (pinfunction "5_5") (pintype "passive"))
      (node (ref "U2") (pin "E7") (pinfunction "P5.1_SPIB_SDIO0_E7") (pintype "bidirectional"))
    )
    (net (code "75") (name "P52_MISO") (class "Default")
      (node (ref "J4") (pin "4") (pinfunction "4_4") (pintype "passive"))
      (node (ref "U2") (pin "C7") (pinfunction "P5.2_SPIB_SDIO1_C7") (pintype "bidirectional"))
    )
    (net (code "76") (name "P53_SSN") (class "Default")
      (node (ref "J5") (pin "8") (pinfunction "8_8") (pintype "passive"))
      (node (ref "U2") (pin "D6") (pinfunction "P5.3_SPIB_SSN0_D6") (pintype "bidirectional"))
    )
    (net (code "77") (name "P54_SDIO2") (class "Default")
      (node (ref "J5") (pin "7") (pinfunction "7_7") (pintype "passive"))
      (node (ref "U2") (pin "C6") (pinfunction "P5.4_SPIB_SDIO2_C6") (pintype "bidirectional"))
    )
    (net (code "78") (name "P55_SDIO3") (class "Default")
      (node (ref "J5") (pin "6") (pinfunction "6_6") (pintype "passive"))
      (node (ref "U2") (pin "C5") (pinfunction "P5.5_SPIB_SDIO3_C5") (pintype "bidirectional"))
    )
    (net (code "79") (name "P56_SRN") (class "Default")
      (node (ref "J5") (pin "5") (pinfunction "5_5") (pintype "passive"))
      (node (ref "U2") (pin "D5") (pinfunction "P5.6_SPIB_SRN_D5") (pintype "bidirectional"))
    )
    (net (code "80") (name "P57_SDA") (class "Default")
      (node (ref "JP4") (pin "2") (pinfunction "2_2") (pintype "bidirectional"))
      (node (ref "R10") (pin "1") (pinfunction "1_1") (pintype "passive"))
      (node (ref "U1") (pin "A3") (pinfunction "SDA_A3") (pintype "bidirectional"))
      (node (ref "U2") (pin "C4") (pinfunction "P5.7_I2CM2/S0C_SDA_C4") (pintype "bidirectional"))
      (node (ref "U5") (pin "C1") (pinfunction "SDA_C1") (pintype "bidirectional"))
    )
    (net (code "81") (name "P60_SCL") (class "Default")
      (node (ref "JP5") (pin "2") (pinfunction "2_2") (pintype "bidirectional"))
      (node (ref "R9") (pin "1") (pinfunction "1_1") (pintype "passive"))
      (node (ref "U1") (pin "B4") (pinfunction "SCL_B4") (pintype "input"))
      (node (ref "U2") (pin "C3") (pinfunction "P6.0_I2CM2/S0C_SCL_C3") (pintype "bidirectional"))
      (node (ref "U5") (pin "A2") (pinfunction "SCL_A2") (pintype "bidirectional"))
    )
    (net (code "82") (name "PVIO") (class "Default")
      (node (ref "C8") (pin "1") (pinfunction "1_1") (pintype "bidirectional"))
      (node (ref "JP6") (pin "2") (pinfunction "2_2") (pintype "bidirectional"))
      (node (ref "P0") (pin "11") (pinfunction "11_11") (pintype "passive"))
      (node (ref "P0") (pin "12") (pinfunction "12_12") (pintype "passive"))
      (node (ref "P1") (pin "11") (pinfunction "11_11") (pintype "passive"))
      (node (ref "P1") (pin "12") (pinfunction "12_12") (pintype "passive"))
    )
    (net (code "83") (name "SWCLK") (class "Default")
      (node (ref "J3") (pin "4") (pinfunction "SWDCLK/TCK_4") (pintype "bidirectional"))
      (node (ref "TP3") (pin "P$1") (pinfunction "P$1_P$1") (pintype "bidirectional"))
      (node (ref "U2") (pin "B4") (pinfunction "TCK/SWC_B4") (pintype "input"))
    )
    (net (code "84") (name "SWDIO") (class "Default")
      (node (ref "J3") (pin "2") (pinfunction "SWDIO/TMS_2") (pintype "bidirectional"))
      (node (ref "TP4") (pin "P$1") (pinfunction "P$1_P$1") (pintype "bidirectional"))
      (node (ref "U2") (pin "B5") (pinfunction "TMS/SWD_B5") (pintype "bidirectional"))
    )
    (net (code "85") (name "SYS") (class "Default")
      (node (ref "C5") (pin "1") (pinfunction "1_1") (pintype "bidirectional"))
      (node (ref "JP1") (pin "1") (pinfunction "1_1") (pintype "bidirectional"))
      (node (ref "R12") (pin "2") (pinfunction "2_2") (pintype "passive"))
      (node (ref "U1") (pin "E2") (pinfunction "SYS_E2") (pintype "power_in"))
      (node (ref "U1") (pin "E4") (pinfunction "IN_SBB_E4") (pintype "power_in"))
    )
    (net (code "86") (name "VBAT") (class "Default")
      (node (ref "C13") (pin "1") (pinfunction "1_1") (pintype "bidirectional"))
      (node (ref "C18") (pin "1") (pinfunction "1_1") (pintype "bidirectional"))
      (node (ref "J2") (pin "2") (pinfunction "2_2") (pintype "passive"))
      (node (ref "JP1") (pin "3") (pinfunction "3_3") (pintype "bidirectional"))
      (node (ref "U1") (pin "E3") (pinfunction "BAT_E3") (pintype "power_in"))
      (node (ref "U5") (pin "B1") (pinfunction "BATT_B1") (pintype "power_in"))
    )
    (net (code "87") (name "VBUS") (class "Default")
      (node (ref "C15") (pin "1") (pinfunction "1_1") (pintype "bidirectional"))
      (node (ref "C9") (pin "1") (pinfunction "1_1") (pintype "bidirectional"))
      (node (ref "J1") (pin "1") (pinfunction "VBUS_1") (pintype "power_in"))
      (node (ref "J5") (pin "3") (pinfunction "3_3") (pintype "passive"))
      (node (ref "U1") (pin "E1") (pinfunction "CHGIN_E1") (pintype "power_in"))
      (node (ref "U4") (pin "5") (pinfunction "VCC_5") (pintype "power_in"))
    )
    (net (code "88") (name "XI") (class "Default")
      (node (ref "U2") (pin "B9") (pinfunction "32KIN_B9") (pintype "input"))
      (node (ref "Y1") (pin "2") (pinfunction "2_2") (pintype "passive"))
    )
    (net (code "89") (name "XO") (class "Default")
      (node (ref "U2") (pin "C9") (pinfunction "32KOUT_C9") (pintype "output"))
      (node (ref "Y1") (pin "1") (pinfunction "1_1") (pintype "passive"))
    )
    (net (code "90") (name "unconnected-(J1-ID-Pad4)") (class "Default")
      (node (ref "J1") (pin "4") (pinfunction "ID_4") (pintype "bidirectional"))
    )
    (net (code "91") (name "unconnected-(J3-KEY-Pad7)") (class "Default")
      (node (ref "J3") (pin "7") (pinfunction "KEY_7") (pintype "bidirectional"))
    )
    (net (code "92") (name "unconnected-(U2A-RST-PadB2)") (class "Default")
      (node (ref "U2") (pin "B2") (pinfunction "RST_B2") (pintype "input"))
    )
    (net (code "93") (name "unconnected-(U2A-TDI-PadB7)") (class "Default")
      (node (ref "U2") (pin "B7") (pinfunction "TDI_B7") (pintype "input"))
    )
    (net (code "94") (name "unconnected-(U2A-TDO-PadB6)") (class "Default")
      (node (ref "U2") (pin "B6") (pinfunction "TDO_B6") (pintype "output"))
    )
    (net (code "95") (name "unconnected-(U2G-P3.7_SPIM1A_SS2-PadF7)") (class "Default")
      (node (ref "U2") (pin "F7") (pinfunction "P3.7_SPIM1A_SS2_F7") (pintype "bidirectional"))
    )
    (net (code "96") (name "unconnected-(U2H-P4.2_SPIM0A_SDIO2-PadH9)") (class "Default")
      (node (ref "U2") (pin "H9") (pinfunction "P4.2_SPIM0A_SDIO2_H9") (pintype "bidirectional"))
    )
    (net (code "97") (name "unconnected-(U2H-P4.3_SPIM0A_SDIO3-PadH8)") (class "Default")
      (node (ref "U2") (pin "H8") (pinfunction "P4.3_SPIM0A_SDIO3_H8") (pintype "bidirectional"))
    )
    (net (code "98") (name "unconnected-(U4-NC-Pad3)") (class "Default")
      (node (ref "U4") (pin "3") (pinfunction "NC_3") (pintype "no_connect"))
    )
    (net (code "99") (name "unconnected-(U4-NC-Pad6)") (class "Default")
      (node (ref "U4") (pin "6") (pinfunction "NC_6") (pintype "no_connect"))
    )
    (net (code "100") (name "unconnected-(U5-THRM-PadC2)") (class "Default")
      (node (ref "U5") (pin "C2") (pinfunction "THRM_C2") (pintype "output"))
    )
    (net (code "101") (name "~{EN}") (class "Default")
      (node (ref "JP2") (pin "2") (pinfunction "2_2") (pintype "bidirectional"))
      (node (ref "R12") (pin "1") (pinfunction "1_1") (pintype "passive"))
      (node (ref "SW2") (pin "2") (pinfunction "2_2") (pintype "bidirectional"))
      (node (ref "U1") (pin "A2") (pinfunction "EN_A2") (pintype "input"))
    )
    (net (code "102") (name "~{RESET}") (class "Default")
      (node (ref "J3") (pin "10") (pinfunction "NRESET_10") (pintype "bidirectional"))
      (node (ref "J4") (pin "16") (pinfunction "16_16") (pintype "passive"))
      (node (ref "R11") (pin "2") (pinfunction "2_2") (pintype "passive"))
      (node (ref "SW3") (pin "2") (pinfunction "2_2") (pintype "bidirectional"))
      (node (ref "U1") (pin "B2") (pinfunction "RST_B2") (pintype "output"))
      (node (ref "U2") (pin "B1") (pinfunction "SRST_B1") (pintype "bidirectional"))
    )
  )
)
